# CAN-IO.net
KiCad netlist of a schematic drawn in Altium Designer
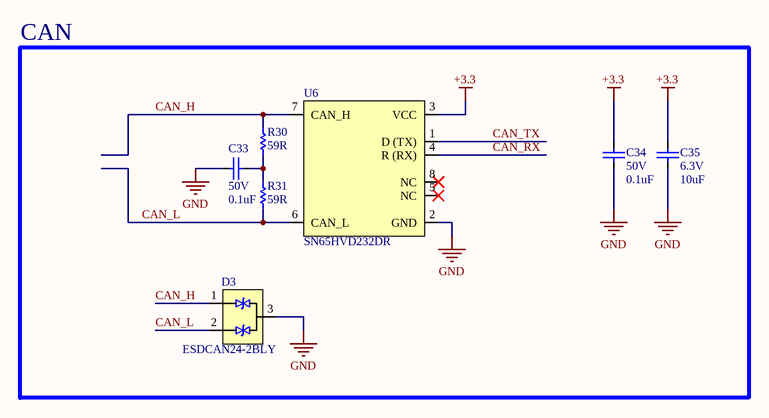
[diagram p0: CAN-IO.SchDoc]

(export (version "E")
  (design (tool "Eeschema 10.0.6"))
  (components
    (comp (ref "C33")
      (value "0.1uF")
      (footprint "CAPACITOR-0603")
      (description "Capacitor-0603-0.1uF-50V-X7R")
      (fields (field (name "VOLT") "50V"))
      (libsource (lib "Capacitors") (part "Capacitor-0603-0.1uF-50V-X7R"))
    )
    (comp (ref "C34")
      (value "0.1uF")
      (footprint "CAPACITOR-0603")
      (description "Capacitor-0603-0.1uF-50V-X7R")
      (fields (field (name "VOLT") "50V"))
      (libsource (lib "Capacitors") (part "Capacitor-0603-0.1uF-50V-X7R"))
    )
    (comp (ref "C35")
      (value "10uF")
      (footprint "CAPACITOR-0603")
      (description "Capacitor-0603-10uF-6.3V-X5R, Low ESR, Low ESL")
      (fields (field (name "VOLT") "6.3V") (field (name "Comment") "Capacitor-0603-10uF-6.3V-X5R"))
      (libsource (lib "Capacitors") (part "Capacitor-0603-10uF-6.3V-X5R"))
    )
    (comp (ref "D3")
      (value "ESDCAN24-2BLY")
      (footprint "SOT-23-3")
      (description "55V Clamp 6A (8/20µs) Ipp Tvs Diode Surface Mount SOT-23")
      (libsource (lib "diodes-tvs") (part "ESDCAN24-2BLY"))
    )
    (comp (ref "R30")
      (value "59R")
      (footprint "Resistor-0603")
      (description "Resistor0603-59R")
      (fields (field (name "Comment") "SMT resistor"))
      (libsource (lib "Resistors") (part "Resistor-0603-59R"))
    )
    (comp (ref "R31")
      (value "59R")
      (footprint "Resistor-0603")
      (description "Resistor0603-59R")
      (fields (field (name "Comment") "SMT resistor"))
      (libsource (lib "Resistors") (part "Resistor-0603-59R"))
    )
    (comp (ref "U6")
      (value "SN65HVD232DR")
      (footprint "SOIC-8")
      (description "1/1 Transceiver Half CANbus 8-SOIC")
      (libsource (lib "Transceiver") (part "SN65HVD232DR"))
    )
  )
  (nets
    (net (code "1") (name "+3.3") (class "Default")
      (node (ref "C34") (pin "2") (pinfunction "2_2") (pintype "passive"))
      (node (ref "C35") (pin "2") (pinfunction "2_2") (pintype "passive"))
      (node (ref "U6") (pin "3") (pinfunction "VCC_3") (pintype "passive"))
    )
    (net (code "2") (name "/CAN_H") (class "Default")
      (node (ref "D3") (pin "1") (pinfunction "L2_1") (pintype "passive"))
      (node (ref "R30") (pin "2") (pinfunction "2_2") (pintype "passive"))
      (node (ref "U6") (pin "7") (pinfunction "CAN_H_7") (pintype "passive"))
    )
    (net (code "3") (name "/CAN_L") (class "Default")
      (node (ref "D3") (pin "2") (pinfunction "GND_2") (pintype "passive"))
      (node (ref "R31") (pin "1") (pinfunction "1_1") (pintype "passive"))
      (node (ref "U6") (pin "6") (pinfunction "CAN_L_6") (pintype "passive"))
    )
    (net (code "4") (name "/CAN_RX") (class "Default")
      (node (ref "U6") (pin "4") (pinfunction "R_(RX)_4") (pintype "passive"))
    )
    (net (code "5") (name "/CAN_TX") (class "Default")
      (node (ref "U6") (pin "1") (pinfunction "D_(TX)_1") (pintype "passive"))
    )
    (net (code "6") (name "GND") (class "Default")
      (node (ref "C33") (pin "1") (pinfunction "1_1") (pintype "passive"))
      (node (ref "C34") (pin "1") (pinfunction "1_1") (pintype "passive"))
      (node (ref "C35") (pin "1") (pinfunction "1_1") (pintype "passive"))
      (node (ref "D3") (pin "3") (pinfunction "L3_3") (pintype "passive"))
      (node (ref "U6") (pin "2") (pinfunction "GND_2") (pintype "passive"))
    )
    (net (code "7") (name "Net-(C33-Pad2)") (class "Default")
      (node (ref "C33") (pin "2") (pinfunction "2_2") (pintype "passive"))
      (node (ref "R30") (pin "1") (pinfunction "1_1") (pintype "passive"))
      (node (ref "R31") (pin "2") (pinfunction "2_2") (pintype "passive"))
    )
    (net (code "8") (name "unconnected-(U6-NC-Pad5)") (class "Default")
      (node (ref "U6") (pin "5") (pinfunction "NC_5") (pintype "passive+no_connect"))
    )
    (net (code "9") (name "unconnected-(U6-NC-Pad8)") (class "Default")
      (node (ref "U6") (pin "8") (pinfunction "NC_8") (pintype "passive+no_connect"))
    )
  )
)
